# Low-Frequency_LC_Oscillator.net
KiCad netlist of a schematic drawn in EAGLE
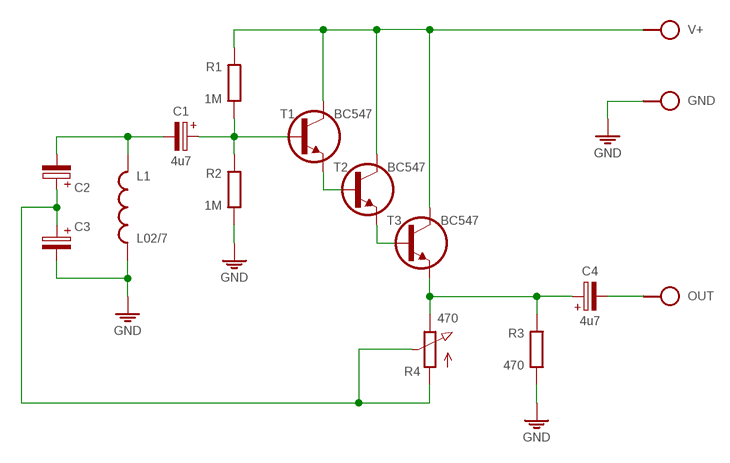
[diagram p0: schematic, sheet 1]

(export (version "E")
  (design (tool "Eeschema 10.0.6"))
  (components
    (comp (ref "C1")
      (value "4u7")
      (footprint "eagle-import:E2,5-3")
      (libsource (lib "eagle-import") (part "CPOLE2,5-3"))
    )
    (comp (ref "C2")
      (value "CPOLE2.5-5")
      (footprint "eagle-import:E2,5-5")
      (libsource (lib "eagle-import") (part "CPOLE2.5-5"))
    )
    (comp (ref "C3")
      (value "CPOLE2.5-5")
      (footprint "eagle-import:E2,5-5")
      (libsource (lib "eagle-import") (part "CPOLE2.5-5"))
    )
    (comp (ref "C4")
      (value "4u7")
      (footprint "eagle-import:E2,5-3")
      (libsource (lib "eagle-import") (part "CPOLE2,5-3"))
    )
    (comp (ref "GND")
      (value "SPAD")
      (footprint "eagle-import:SPAD")
      (libsource (lib "eagle-import") (part "SPAD"))
    )
    (comp (ref "L1")
      (value "L02/7")
      (footprint "eagle-import:L-02_7V")
      (libsource (lib "eagle-import") (part "L02/7"))
    )
    (comp (ref "OUT")
      (value "SPAD")
      (footprint "eagle-import:SPAD")
      (libsource (lib "eagle-import") (part "SPAD"))
    )
    (comp (ref "R1")
      (value "1M")
      (footprint "eagle-import:0204_10")
      (libsource (lib "eagle-import") (part "R0204/10"))
    )
    (comp (ref "R2")
      (value "1M")
      (footprint "eagle-import:0204_10")
      (libsource (lib "eagle-import") (part "R0204/10"))
    )
    (comp (ref "R3")
      (value "470")
      (footprint "eagle-import:0204_10")
      (libsource (lib "eagle-import") (part "R0204/10"))
    )
    (comp (ref "R4")
      (value "470")
      (footprint "eagle-import:POT")
      (libsource (lib "eagle-import") (part "POT"))
    )
    (comp (ref "T1")
      (value "BC547")
      (footprint "eagle-import:TO92-CBE")
      (libsource (lib "eagle-import") (part "BC547CBE"))
    )
    (comp (ref "T2")
      (value "BC547")
      (footprint "eagle-import:TO92-CBE")
      (libsource (lib "eagle-import") (part "BC547CBE"))
    )
    (comp (ref "T3")
      (value "BC547")
      (footprint "eagle-import:TO92-CBE")
      (libsource (lib "eagle-import") (part "BC547CBE"))
    )
    (comp (ref "V+")
      (value "SPAD")
      (footprint "eagle-import:SPAD")
      (libsource (lib "eagle-import") (part "SPAD"))
    )
  )
  (nets
    (net (code "1") (name "GND") (class "Default")
      (node (ref "C3") (pin "-") (pinfunction "-_-") (pintype "passive"))
      (node (ref "GND") (pin "1") (pinfunction "P$1_1") (pintype "bidirectional"))
      (node (ref "L1") (pin "2") (pinfunction "2_2") (pintype "passive"))
      (node (ref "R2") (pin "1") (pinfunction "1_1") (pintype "passive"))
      (node (ref "R3") (pin "1") (pinfunction "1_1") (pintype "passive"))
    )
    (net (code "2") (name "Net-(C1-Pad+)") (class "Default")
      (node (ref "C1") (pin "+") (pinfunction "+_+") (pintype "passive"))
      (node (ref "R1") (pin "1") (pinfunction "1_1") (pintype "passive"))
      (node (ref "R2") (pin "2") (pinfunction "2_2") (pintype "passive"))
      (node (ref "T1") (pin "B") (pinfunction "B_B") (pintype "passive"))
    )
    (net (code "3") (name "Net-(C1-Pad-)") (class "Default")
      (node (ref "C1") (pin "-") (pinfunction "-_-") (pintype "passive"))
      (node (ref "C2") (pin "-") (pinfunction "-_-") (pintype "passive"))
      (node (ref "L1") (pin "1") (pinfunction "1_1") (pintype "passive"))
    )
    (net (code "4") (name "Net-(OUT-P$1)") (class "Default")
      (node (ref "C4") (pin "-") (pinfunction "-_-") (pintype "passive"))
      (node (ref "OUT") (pin "1") (pinfunction "P$1_1") (pintype "bidirectional"))
    )
    (net (code "5") (name "Net-(R4-A)") (class "Default")
      (node (ref "C2") (pin "+") (pinfunction "+_+") (pintype "passive"))
      (node (ref "C3") (pin "+") (pinfunction "+_+") (pintype "passive"))
      (node (ref "R4") (pin "1") (pinfunction "A_1") (pintype "passive"))
      (node (ref "R4") (pin "2") (pinfunction "S_2") (pintype "passive"))
    )
    (net (code "6") (name "Net-(R4-E)") (class "Default")
      (node (ref "C4") (pin "+") (pinfunction "+_+") (pintype "passive"))
      (node (ref "R3") (pin "2") (pinfunction "2_2") (pintype "passive"))
      (node (ref "R4") (pin "3") (pinfunction "E_3") (pintype "passive"))
      (node (ref "T3") (pin "E") (pinfunction "E_E") (pintype "passive"))
    )
    (net (code "7") (name "Net-(T1-PadE)") (class "Default")
      (node (ref "T1") (pin "E") (pinfunction "E_E") (pintype "passive"))
      (node (ref "T2") (pin "B") (pinfunction "B_B") (pintype "passive"))
    )
    (net (code "8") (name "Net-(T2-PadE)") (class "Default")
      (node (ref "T2") (pin "E") (pinfunction "E_E") (pintype "passive"))
      (node (ref "T3") (pin "B") (pinfunction "B_B") (pintype "passive"))
    )
    (net (code "9") (name "Net-(V+-P$1)") (class "Default")
      (node (ref "R1") (pin "2") (pinfunction "2_2") (pintype "passive"))
      (node (ref "T1") (pin "C") (pinfunction "C_C") (pintype "passive"))
      (node (ref "T2") (pin "C") (pinfunction "C_C") (pintype "passive"))
      (node (ref "T3") (pin "C") (pinfunction "C_C") (pintype "passive"))
      (node (ref "V+") (pin "1") (pinfunction "P$1_1") (pintype "bidirectional"))
    )
  )
)
